# projector-cooling.net
KiCad netlist of a schematic drawn in EAGLE
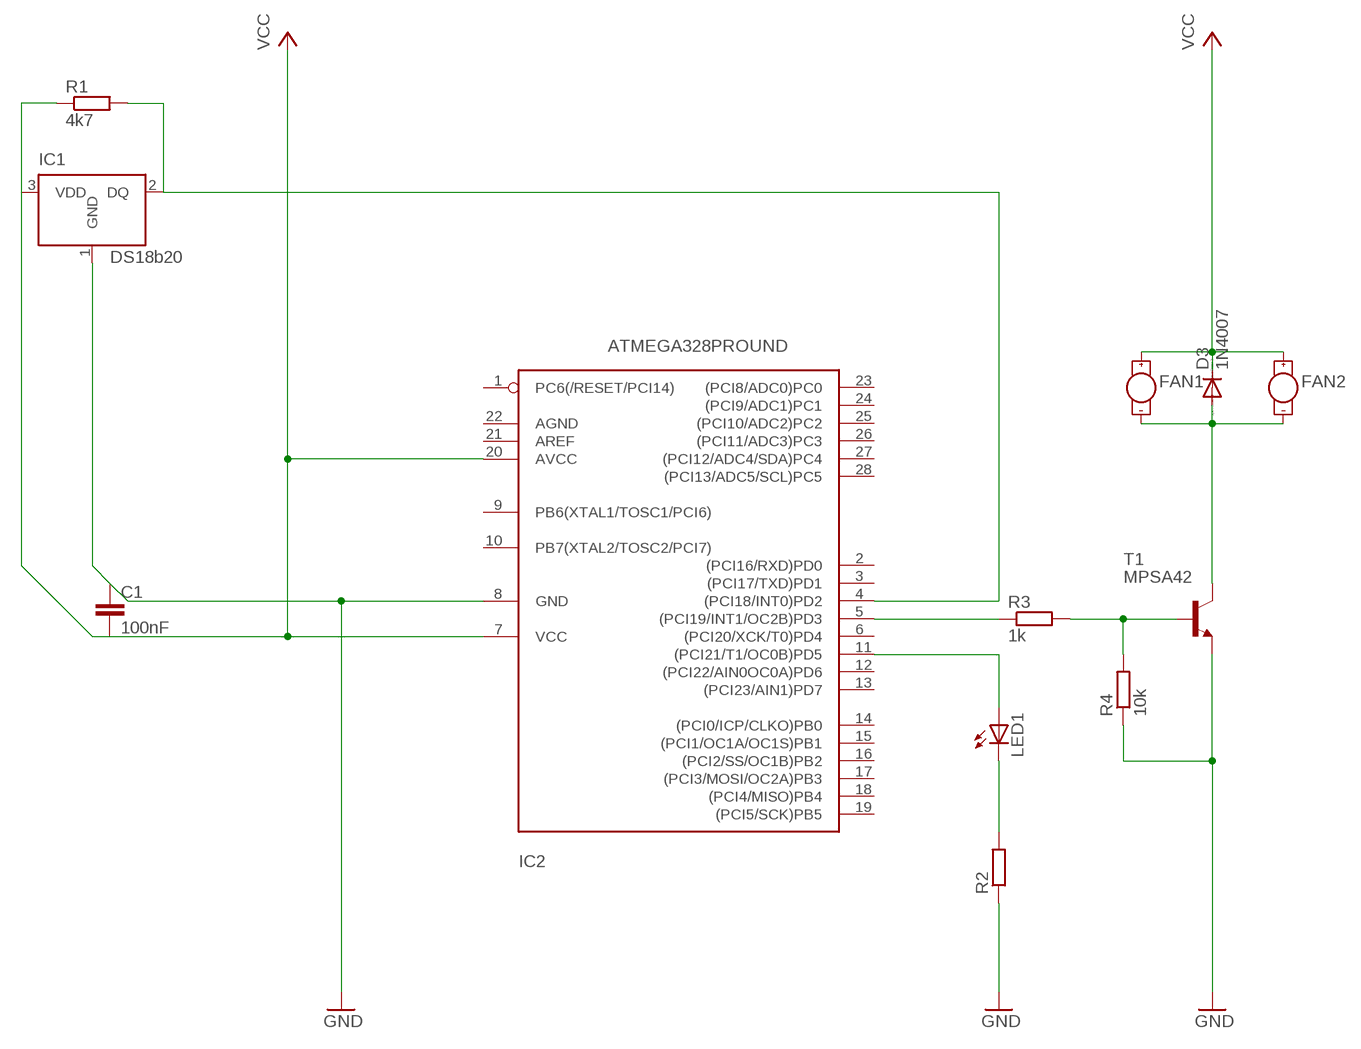
[diagram p0: schematic, sheet 1]

(export (version "E")
  (design (tool "Eeschema 10.0.6"))
  (components
    (comp (ref "C1")
      (value "100nF")
      (footprint "eagle-import:C5B2.5")
      (libsource (lib "eagle-import") (part "C5/2.5"))
    )
    (comp (ref "D3")
      (value "1N4007")
      (footprint "eagle-import:DO41-10")
      (libsource (lib "eagle-import") (part "1N4004"))
    )
    (comp (ref "FAN1")
      (value "MOTOR10MM")
      (footprint "eagle-import:VIBE-MOTOR-10MM")
      (libsource (lib "eagle-import") (part "MOTOR10MM"))
    )
    (comp (ref "FAN2")
      (value "MOTOR10MM")
      (footprint "eagle-import:VIBE-MOTOR-10MM")
      (libsource (lib "eagle-import") (part "MOTOR10MM"))
    )
    (comp (ref "IC1")
      (value "DS18b20")
      (footprint "eagle-import:TO-92")
      (libsource (lib "eagle-import") (part "DS1820"))
    )
    (comp (ref "IC2")
      (value "ATMEGA328PROUND")
      (footprint "eagle-import:DIL28-3-ROUND")
      (libsource (lib "eagle-import") (part "ATMEGA328PROUND"))
    )
    (comp (ref "LED1")
      (value "LED3MM")
      (footprint "eagle-import:LED3MM")
      (libsource (lib "eagle-import") (part "LED3MM"))
    )
    (comp (ref "R1")
      (value "4k7")
      (footprint "eagle-import:0204_7")
      (libsource (lib "eagle-import") (part "R-EU_0204/7"))
    )
    (comp (ref "R2")
      (value "R-EU_0204/5")
      (footprint "eagle-import:0204_5")
      (libsource (lib "eagle-import") (part "R-EU_0204/5"))
    )
    (comp (ref "R3")
      (value "1k")
      (footprint "eagle-import:0204_5")
      (libsource (lib "eagle-import") (part "R-EU_0204/5"))
    )
    (comp (ref "R4")
      (value "10k")
      (footprint "eagle-import:0204_5")
      (libsource (lib "eagle-import") (part "R-EU_0204/5"))
    )
    (comp (ref "T1")
      (value "MPSA42")
      (footprint "eagle-import:TO92")
      (libsource (lib "eagle-import") (part "2N3704"))
    )
  )
  (nets
    (net (code "1") (name "GND") (class "Default")
      (node (ref "C1") (pin "1") (pinfunction "1_1") (pintype "passive"))
      (node (ref "IC1") (pin "1") (pinfunction "GND_1") (pintype "power_in"))
      (node (ref "IC2") (pin "8") (pinfunction "GND_8") (pintype "bidirectional"))
      (node (ref "R2") (pin "1") (pinfunction "1_1") (pintype "passive"))
      (node (ref "R4") (pin "1") (pinfunction "1_1") (pintype "passive"))
      (node (ref "T1") (pin "3") (pinfunction "E_3") (pintype "passive"))
    )
    (net (code "2") (name "Net-(IC1-DQ)") (class "Default")
      (node (ref "IC1") (pin "2") (pinfunction "DQ_2") (pintype "output"))
      (node (ref "IC2") (pin "4") (pinfunction "(PCI18/INT0)PD2_4") (pintype "bidirectional"))
      (node (ref "R1") (pin "2") (pinfunction "2_2") (pintype "passive"))
    )
    (net (code "3") (name "Net-(IC2-(PCI19{slash}INT1{slash}OC2B)PD3)") (class "Default")
      (node (ref "IC2") (pin "5") (pinfunction "(PCI19/INT1/OC2B)PD3_5") (pintype "bidirectional"))
      (node (ref "R3") (pin "1") (pinfunction "1_1") (pintype "passive"))
    )
    (net (code "4") (name "Net-(IC2-(PCI21{slash}T1{slash}OC0B)PD5)") (class "Default")
      (node (ref "IC2") (pin "11") (pinfunction "(PCI21/T1/OC0B)PD5_11") (pintype "bidirectional"))
      (node (ref "LED1") (pin "A") (pinfunction "A_A") (pintype "passive"))
    )
    (net (code "5") (name "Net-(LED1-C)") (class "Default")
      (node (ref "LED1") (pin "K") (pinfunction "C_K") (pintype "passive"))
      (node (ref "R2") (pin "2") (pinfunction "2_2") (pintype "passive"))
    )
    (net (code "6") (name "Net-(T1-B)") (class "Default")
      (node (ref "R3") (pin "2") (pinfunction "2_2") (pintype "passive"))
      (node (ref "R4") (pin "2") (pinfunction "2_2") (pintype "passive"))
      (node (ref "T1") (pin "1") (pinfunction "B_1") (pintype "passive"))
    )
    (net (code "7") (name "Net-(T1-C)") (class "Default")
      (node (ref "D3") (pin "A") (pinfunction "A_A") (pintype "passive"))
      (node (ref "FAN1") (pin "-") (pinfunction "-_-") (pintype "bidirectional"))
      (node (ref "FAN2") (pin "-") (pinfunction "-_-") (pintype "bidirectional"))
      (node (ref "T1") (pin "2") (pinfunction "C_2") (pintype "passive"))
    )
    (net (code "8") (name "VCC") (class "Default")
      (node (ref "C1") (pin "2") (pinfunction "2_2") (pintype "passive"))
      (node (ref "D3") (pin "C") (pinfunction "C_C") (pintype "passive"))
      (node (ref "FAN1") (pin "+") (pinfunction "+_+") (pintype "bidirectional"))
      (node (ref "FAN2") (pin "+") (pinfunction "+_+") (pintype "bidirectional"))
      (node (ref "IC1") (pin "3") (pinfunction "VDD_3") (pintype "input"))
      (node (ref "IC2") (pin "20") (pinfunction "AVCC_20") (pintype "bidirectional"))
      (node (ref "IC2") (pin "7") (pinfunction "VCC_7") (pintype "bidirectional"))
      (node (ref "R1") (pin "1") (pinfunction "1_1") (pintype "passive"))
    )
    (net (code "9") (name "unconnected-(IC2-(PCI0{slash}ICP{slash}CLKO)PB0-Pad14)") (class "Default")
      (node (ref "IC2") (pin "14") (pinfunction "(PCI0/ICP/CLKO)PB0_14") (pintype "bidirectional"))
    )
    (net (code "10") (name "unconnected-(IC2-(PCI1{slash}OC1A{slash}OC1S)PB1-Pad15)") (class "Default")
      (node (ref "IC2") (pin "15") (pinfunction "(PCI1/OC1A/OC1S)PB1_15") (pintype "bidirectional"))
    )
    (net (code "11") (name "unconnected-(IC2-(PCI2{slash}SS{slash}OC1B)PB2-Pad16)") (class "Default")
      (node (ref "IC2") (pin "16") (pinfunction "(PCI2/SS/OC1B)PB2_16") (pintype "bidirectional"))
    )
    (net (code "12") (name "unconnected-(IC2-(PCI3{slash}MOSI{slash}OC2A)PB3-Pad17)") (class "Default")
      (node (ref "IC2") (pin "17") (pinfunction "(PCI3/MOSI/OC2A)PB3_17") (pintype "bidirectional"))
    )
    (net (code "13") (name "unconnected-(IC2-(PCI4{slash}MISO)PB4-Pad18)") (class "Default")
      (node (ref "IC2") (pin "18") (pinfunction "(PCI4/MISO)PB4_18") (pintype "bidirectional"))
    )
    (net (code "14") (name "unconnected-(IC2-(PCI5{slash}SCK)PB5-Pad19)") (class "Default")
      (node (ref "IC2") (pin "19") (pinfunction "(PCI5/SCK)PB5_19") (pintype "bidirectional"))
    )
    (net (code "15") (name "unconnected-(IC2-(PCI8{slash}ADC0)PC0-Pad23)") (class "Default")
      (node (ref "IC2") (pin "23") (pinfunction "(PCI8/ADC0)PC0_23") (pintype "bidirectional"))
    )
    (net (code "16") (name "unconnected-(IC2-(PCI9{slash}ADC1)PC1-Pad24)") (class "Default")
      (node (ref "IC2") (pin "24") (pinfunction "(PCI9/ADC1)PC1_24") (pintype "bidirectional"))
    )
    (net (code "17") (name "unconnected-(IC2-(PCI10{slash}ADC2)PC2-Pad25)") (class "Default")
      (node (ref "IC2") (pin "25") (pinfunction "(PCI10/ADC2)PC2_25") (pintype "bidirectional"))
    )
    (net (code "18") (name "unconnected-(IC2-(PCI11{slash}ADC3)PC3-Pad26)") (class "Default")
      (node (ref "IC2") (pin "26") (pinfunction "(PCI11/ADC3)PC3_26") (pintype "bidirectional"))
    )
    (net (code "19") (name "unconnected-(IC2-(PCI12{slash}ADC4{slash}SDA)PC4-Pad27)") (class "Default")
      (node (ref "IC2") (pin "27") (pinfunction "(PCI12/ADC4/SDA)PC4_27") (pintype "bidirectional"))
    )
    (net (code "20") (name "unconnected-(IC2-(PCI13{slash}ADC5{slash}SCL)PC5-Pad28)") (class "Default")
      (node (ref "IC2") (pin "28") (pinfunction "(PCI13/ADC5/SCL)PC5_28") (pintype "bidirectional"))
    )
    (net (code "21") (name "unconnected-(IC2-(PCI16{slash}RXD)PD0-Pad2)") (class "Default")
      (node (ref "IC2") (pin "2") (pinfunction "(PCI16/RXD)PD0_2") (pintype "bidirectional"))
    )
    (net (code "22") (name "unconnected-(IC2-(PCI17{slash}TXD)PD1-Pad3)") (class "Default")
      (node (ref "IC2") (pin "3") (pinfunction "(PCI17/TXD)PD1_3") (pintype "bidirectional"))
    )
    (net (code "23") (name "unconnected-(IC2-(PCI20{slash}XCK{slash}T0)PD4-Pad6)") (class "Default")
      (node (ref "IC2") (pin "6") (pinfunction "(PCI20/XCK/T0)PD4_6") (pintype "bidirectional"))
    )
    (net (code "24") (name "unconnected-(IC2-(PCI22{slash}AIN0OC0A)PD6-Pad12)") (class "Default")
      (node (ref "IC2") (pin "12") (pinfunction "(PCI22/AIN0OC0A)PD6_12") (pintype "bidirectional"))
    )
    (net (code "25") (name "unconnected-(IC2-(PCI23{slash}AIN1)PD7-Pad13)") (class "Default")
      (node (ref "IC2") (pin "13") (pinfunction "(PCI23/AIN1)PD7_13") (pintype "bidirectional"))
    )
    (net (code "26") (name "unconnected-(IC2-AGND-Pad22)") (class "Default")
      (node (ref "IC2") (pin "22") (pinfunction "AGND_22") (pintype "bidirectional"))
    )
    (net (code "27") (name "unconnected-(IC2-AREF-Pad21)") (class "Default")
      (node (ref "IC2") (pin "21") (pinfunction "AREF_21") (pintype "bidirectional"))
    )
    (net (code "28") (name "unconnected-(IC2-PB6(XTAL1{slash}TOSC1{slash}PCI6)-Pad9)") (class "Default")
      (node (ref "IC2") (pin "9") (pinfunction "PB6(XTAL1/TOSC1/PCI6)_9") (pintype "bidirectional"))
    )
    (net (code "29") (name "unconnected-(IC2-PB7(XTAL2{slash}TOSC2{slash}PCI7)-Pad10)") (class "Default")
      (node (ref "IC2") (pin "10") (pinfunction "PB7(XTAL2/TOSC2/PCI7)_10") (pintype "bidirectional"))
    )
    (net (code "30") (name "unconnected-(IC2-PC6({slash}RESET{slash}PCI14)-Pad1)") (class "Default")
      (node (ref "IC2") (pin "1") (pinfunction "PC6(/RESET/PCI14)_1") (pintype "bidirectional"))
    )
  )
)
